# XBee_Explorer_USB.net
KiCad netlist of a schematic drawn in EAGLE
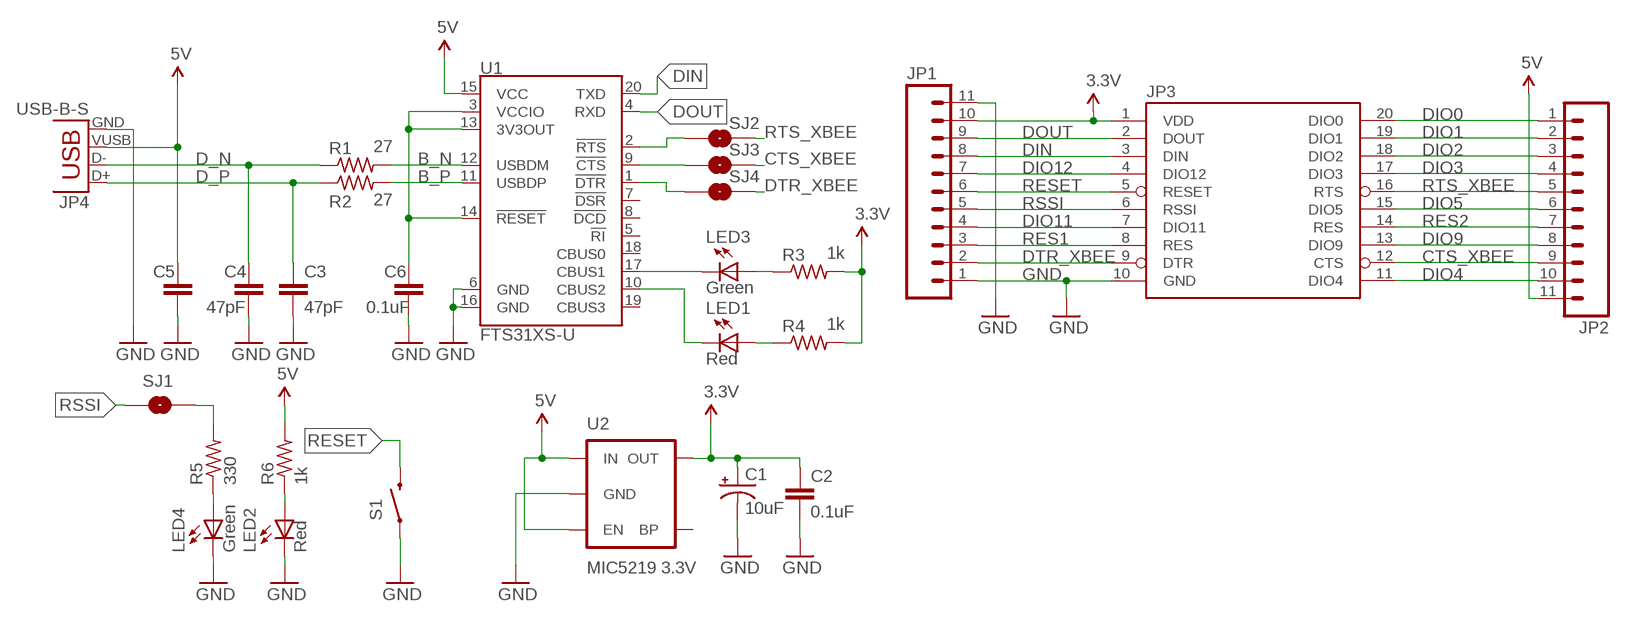
[diagram p0: schematic, sheet 1]

(export (version "E")
  (design (tool "Eeschema 10.0.6"))
  (components
    (comp (ref "C1")
      (value "10uF")
      (footprint "eagle-import:EIA3216")
      (libsource (lib "eagle-import") (part "10UF-16V-10%(TANT)"))
    )
    (comp (ref "C2")
      (value "0.1uF")
      (footprint "eagle-import:0805")
      (libsource (lib "eagle-import") (part "CAP0805"))
    )
    (comp (ref "C3")
      (value "47pF")
      (footprint "eagle-import:0805")
      (libsource (lib "eagle-import") (part "CAP0805"))
    )
    (comp (ref "C4")
      (value "47pF")
      (footprint "eagle-import:0805")
      (libsource (lib "eagle-import") (part "CAP0805"))
    )
    (comp (ref "C5")
      (value "CAP0805")
      (footprint "eagle-import:0805")
      (libsource (lib "eagle-import") (part "CAP0805"))
    )
    (comp (ref "C6")
      (value "0.1uF")
      (footprint "eagle-import:0805")
      (libsource (lib "eagle-import") (part "CAP0805"))
    )
    (comp (ref "JP1")
      (value "M111X11_NO_SILK")
      (footprint "eagle-import:1X11_NO_SILK")
      (libsource (lib "eagle-import") (part "M111X11_NO_SILK"))
    )
    (comp (ref "JP2")
      (value "M111X11_NO_SILK")
      (footprint "eagle-import:1X11_NO_SILK")
      (libsource (lib "eagle-import") (part "M111X11_NO_SILK"))
    )
    (comp (ref "JP3")
      (value "XBEE-1B3")
      (footprint "eagle-import:XBEE-SMD")
      (libsource (lib "eagle-import") (part "XBEE-1B3"))
    )
    (comp (ref "JP4")
      (value "USB-B-S")
      (footprint "eagle-import:USB-B-SMT")
      (libsource (lib "eagle-import") (part "USB-B-S"))
    )
    (comp (ref "LED1")
      (value "Red")
      (footprint "eagle-import:CHIP-LED0805")
      (libsource (lib "eagle-import") (part "LEDCHIP-LED0805"))
    )
    (comp (ref "LED2")
      (value "Red")
      (footprint "eagle-import:CHIP-LED0805")
      (libsource (lib "eagle-import") (part "LEDCHIP-LED0805"))
    )
    (comp (ref "LED3")
      (value "Green")
      (footprint "eagle-import:CHIP-LED0805")
      (libsource (lib "eagle-import") (part "LEDCHIP-LED0805"))
    )
    (comp (ref "LED4")
      (value "Green")
      (footprint "eagle-import:CHIP-LED0805")
      (libsource (lib "eagle-import") (part "LEDCHIP-LED0805"))
    )
    (comp (ref "R1")
      (value "27")
      (footprint "eagle-import:R0805")
      (libsource (lib "eagle-import") (part "R-US_R0805"))
    )
    (comp (ref "R2")
      (value "27")
      (footprint "eagle-import:R0805")
      (libsource (lib "eagle-import") (part "R-US_R0805"))
    )
    (comp (ref "R3")
      (value "1k")
      (footprint "eagle-import:R0805")
      (libsource (lib "eagle-import") (part "R-US_R0805"))
    )
    (comp (ref "R4")
      (value "1k")
      (footprint "eagle-import:R0805")
      (libsource (lib "eagle-import") (part "R-US_R0805"))
    )
    (comp (ref "R5")
      (value "330")
      (footprint "eagle-import:R0805")
      (libsource (lib "eagle-import") (part "R-US_R0805"))
    )
    (comp (ref "R6")
      (value "1k")
      (footprint "eagle-import:R0805")
      (libsource (lib "eagle-import") (part "R-US_R0805"))
    )
    (comp (ref "S1")
      (value "SWITCH-MOMENTARY-2SMD")
      (footprint "eagle-import:TACTILE-SWITCH-SMD")
      (libsource (lib "eagle-import") (part "SWITCH-MOMENTARY-2SMD"))
    )
    (comp (ref "SJ1")
      (value "SOLDERJUMPERTRACE")
      (footprint "eagle-import:SJ_2S-TRACE")
      (libsource (lib "eagle-import") (part "SOLDERJUMPERTRACE"))
    )
    (comp (ref "SJ2")
      (value "SOLDERJUMPERTRACE")
      (footprint "eagle-import:SJ_2S-TRACE")
      (libsource (lib "eagle-import") (part "SOLDERJUMPERTRACE"))
    )
    (comp (ref "SJ3")
      (value "SOLDERJUMPERTRACE")
      (footprint "eagle-import:SJ_2S-TRACE")
      (libsource (lib "eagle-import") (part "SOLDERJUMPERTRACE"))
    )
    (comp (ref "SJ4")
      (value "SOLDERJUMPERTRACE")
      (footprint "eagle-import:SJ_2S-TRACE")
      (libsource (lib "eagle-import") (part "SOLDERJUMPERTRACE"))
    )
    (comp (ref "U1")
      (value "FTS31XS-U")
      (footprint "eagle-import:SSOP20_L")
      (libsource (lib "eagle-import") (part "FT231XS"))
    )
    (comp (ref "U2")
      (value "MIC5219 3.3V")
      (footprint "eagle-import:SOT23-5")
      (libsource (lib "eagle-import") (part "V_REG_MIC52193.3V"))
    )
  )
  (nets
    (net (code "1") (name "/B_N") (class "Default")
      (node (ref "R1") (pin "2") (pinfunction "2_2") (pintype "passive"))
      (node (ref "U1") (pin "12") (pinfunction "USBDM_12") (pintype "bidirectional"))
    )
    (net (code "2") (name "/B_P") (class "Default")
      (node (ref "R2") (pin "2") (pinfunction "2_2") (pintype "passive"))
      (node (ref "U1") (pin "11") (pinfunction "USBDP_11") (pintype "bidirectional"))
    )
    (net (code "3") (name "/CTS_XBEE") (class "Default")
      (node (ref "JP2") (pin "9") (pinfunction "9_9") (pintype "passive"))
      (node (ref "JP3") (pin "12") (pinfunction "CTS_12") (pintype "output"))
      (node (ref "SJ3") (pin "2") (pinfunction "2_2") (pintype "passive"))
    )
    (net (code "4") (name "/DIO0") (class "Default")
      (node (ref "JP2") (pin "1") (pinfunction "1_1") (pintype "passive"))
      (node (ref "JP3") (pin "20") (pinfunction "DIO0_20") (pintype "bidirectional"))
    )
    (net (code "5") (name "/DIO1") (class "Default")
      (node (ref "JP2") (pin "2") (pinfunction "2_2") (pintype "passive"))
      (node (ref "JP3") (pin "19") (pinfunction "DIO1_19") (pintype "bidirectional"))
    )
    (net (code "6") (name "/DIO2") (class "Default")
      (node (ref "JP2") (pin "3") (pinfunction "3_3") (pintype "passive"))
      (node (ref "JP3") (pin "18") (pinfunction "DIO2_18") (pintype "bidirectional"))
    )
    (net (code "7") (name "/DIO3") (class "Default")
      (node (ref "JP2") (pin "4") (pinfunction "4_4") (pintype "passive"))
      (node (ref "JP3") (pin "17") (pinfunction "DIO3_17") (pintype "bidirectional"))
    )
    (net (code "8") (name "/DIO4") (class "Default")
      (node (ref "JP2") (pin "10") (pinfunction "10_10") (pintype "passive"))
      (node (ref "JP3") (pin "11") (pinfunction "DIO4_11") (pintype "bidirectional"))
    )
    (net (code "9") (name "/DIO5") (class "Default")
      (node (ref "JP2") (pin "6") (pinfunction "6_6") (pintype "passive"))
      (node (ref "JP3") (pin "15") (pinfunction "DIO5_15") (pintype "bidirectional"))
    )
    (net (code "10") (name "/DIO9") (class "Default")
      (node (ref "JP2") (pin "8") (pinfunction "8_8") (pintype "passive"))
      (node (ref "JP3") (pin "13") (pinfunction "DIO9_13") (pintype "bidirectional"))
    )
    (net (code "11") (name "/DIO11") (class "Default")
      (node (ref "JP1") (pin "4") (pinfunction "4_4") (pintype "passive"))
      (node (ref "JP3") (pin "7") (pinfunction "DIO11_7") (pintype "bidirectional"))
    )
    (net (code "12") (name "/DIO12") (class "Default")
      (node (ref "JP1") (pin "7") (pinfunction "7_7") (pintype "passive"))
      (node (ref "JP3") (pin "4") (pinfunction "DIO12_4") (pintype "bidirectional"))
    )
    (net (code "13") (name "/DTR_XBEE") (class "Default")
      (node (ref "JP1") (pin "2") (pinfunction "2_2") (pintype "passive"))
      (node (ref "JP3") (pin "9") (pinfunction "DTR_9") (pintype "bidirectional"))
      (node (ref "SJ4") (pin "2") (pinfunction "2_2") (pintype "passive"))
    )
    (net (code "14") (name "/D_N") (class "Default")
      (node (ref "C4") (pin "1") (pinfunction "1_1") (pintype "passive"))
      (node (ref "JP4") (pin "D-") (pinfunction "D-_D-") (pintype "bidirectional"))
      (node (ref "R1") (pin "1") (pinfunction "1_1") (pintype "passive"))
    )
    (net (code "15") (name "/D_P") (class "Default")
      (node (ref "C3") (pin "1") (pinfunction "1_1") (pintype "passive"))
      (node (ref "JP4") (pin "D+") (pinfunction "D+_D+") (pintype "bidirectional"))
      (node (ref "R2") (pin "1") (pinfunction "1_1") (pintype "passive"))
    )
    (net (code "16") (name "/RES1") (class "Default")
      (node (ref "JP1") (pin "3") (pinfunction "3_3") (pintype "passive"))
      (node (ref "JP3") (pin "8") (pinfunction "RES_8") (pintype "bidirectional"))
    )
    (net (code "17") (name "/RES2") (class "Default")
      (node (ref "JP2") (pin "7") (pinfunction "7_7") (pintype "passive"))
      (node (ref "JP3") (pin "14") (pinfunction "RES_14") (pintype "bidirectional"))
    )
    (net (code "18") (name "/RTS_XBEE") (class "Default")
      (node (ref "JP2") (pin "5") (pinfunction "5_5") (pintype "passive"))
      (node (ref "JP3") (pin "16") (pinfunction "RTS_16") (pintype "input"))
      (node (ref "SJ2") (pin "2") (pinfunction "2_2") (pintype "passive"))
    )
    (net (code "19") (name "3.3V") (class "Default")
      (node (ref "C1") (pin "A") (pinfunction "+_A") (pintype "passive"))
      (node (ref "C2") (pin "1") (pinfunction "1_1") (pintype "passive"))
      (node (ref "JP1") (pin "10") (pinfunction "10_10") (pintype "passive"))
      (node (ref "JP3") (pin "1") (pinfunction "VDD_1") (pintype "power_in"))
      (node (ref "R3") (pin "2") (pinfunction "2_2") (pintype "passive"))
      (node (ref "R4") (pin "2") (pinfunction "2_2") (pintype "passive"))
      (node (ref "U2") (pin "5") (pinfunction "OUT_5") (pintype "passive"))
    )
    (net (code "20") (name "5V") (class "Default")
      (node (ref "C5") (pin "1") (pinfunction "1_1") (pintype "passive"))
      (node (ref "JP2") (pin "11") (pinfunction "11_11") (pintype "passive"))
      (node (ref "JP4") (pin "VUSB") (pinfunction "VBUS_VUSB") (pintype "bidirectional"))
      (node (ref "R6") (pin "2") (pinfunction "2_2") (pintype "passive"))
      (node (ref "U1") (pin "15") (pinfunction "VCC_15") (pintype "bidirectional"))
      (node (ref "U2") (pin "1") (pinfunction "IN_1") (pintype "input"))
      (node (ref "U2") (pin "3") (pinfunction "EN_3") (pintype "input"))
    )
    (net (code "21") (name "DIN") (class "Default")
      (node (ref "JP1") (pin "8") (pinfunction "8_8") (pintype "passive"))
      (node (ref "JP3") (pin "3") (pinfunction "DIN_3") (pintype "input"))
      (node (ref "U1") (pin "20") (pinfunction "TXD_20") (pintype "bidirectional"))
    )
    (net (code "22") (name "DOUT") (class "Default")
      (node (ref "JP1") (pin "9") (pinfunction "9_9") (pintype "passive"))
      (node (ref "JP3") (pin "2") (pinfunction "DOUT_2") (pintype "output"))
      (node (ref "U1") (pin "4") (pinfunction "RXD_4") (pintype "bidirectional"))
    )
    (net (code "23") (name "GND") (class "Default")
      (node (ref "C1") (pin "C") (pinfunction "-_C") (pintype "passive"))
      (node (ref "C2") (pin "2") (pinfunction "2_2") (pintype "passive"))
      (node (ref "C3") (pin "2") (pinfunction "2_2") (pintype "passive"))
      (node (ref "C4") (pin "2") (pinfunction "2_2") (pintype "passive"))
      (node (ref "C5") (pin "2") (pinfunction "2_2") (pintype "passive"))
      (node (ref "C6") (pin "2") (pinfunction "2_2") (pintype "passive"))
      (node (ref "JP1") (pin "1") (pinfunction "1_1") (pintype "passive"))
      (node (ref "JP1") (pin "11") (pinfunction "11_11") (pintype "passive"))
      (node (ref "JP3") (pin "10") (pinfunction "GND_10") (pintype "power_in"))
      (node (ref "JP4") (pin "GND") (pinfunction "GND_GND") (pintype "bidirectional"))
      (node (ref "LED2") (pin "C") (pinfunction "C_C") (pintype "passive"))
      (node (ref "LED4") (pin "C") (pinfunction "C_C") (pintype "passive"))
      (node (ref "S1") (pin "1") (pinfunction "1_1") (pintype "passive"))
      (node (ref "U1") (pin "16") (pinfunction "GND_16") (pintype "bidirectional"))
      (node (ref "U1") (pin "6") (pinfunction "GND_6") (pintype "bidirectional"))
      (node (ref "U2") (pin "2") (pinfunction "GND_2") (pintype "input"))
    )
    (net (code "24") (name "Net-(LED1-PadA)") (class "Default")
      (node (ref "LED1") (pin "A") (pinfunction "A_A") (pintype "passive"))
      (node (ref "R4") (pin "1") (pinfunction "1_1") (pintype "passive"))
    )
    (net (code "25") (name "Net-(LED2-PadA)") (class "Default")
      (node (ref "LED2") (pin "A") (pinfunction "A_A") (pintype "passive"))
      (node (ref "R6") (pin "1") (pinfunction "1_1") (pintype "passive"))
    )
    (net (code "26") (name "Net-(LED3-PadA)") (class "Default")
      (node (ref "LED3") (pin "A") (pinfunction "A_A") (pintype "passive"))
      (node (ref "R3") (pin "1") (pinfunction "1_1") (pintype "passive"))
    )
    (net (code "27") (name "Net-(LED4-PadA)") (class "Default")
      (node (ref "LED4") (pin "A") (pinfunction "A_A") (pintype "passive"))
      (node (ref "R5") (pin "1") (pinfunction "1_1") (pintype "passive"))
    )
    (net (code "28") (name "Net-(R5-Pad2)") (class "Default")
      (node (ref "R5") (pin "2") (pinfunction "2_2") (pintype "passive"))
      (node (ref "SJ1") (pin "2") (pinfunction "2_2") (pintype "passive"))
    )
    (net (code "29") (name "Net-(U1-3V3OUT)") (class "Default")
      (node (ref "C6") (pin "1") (pinfunction "1_1") (pintype "passive"))
      (node (ref "U1") (pin "13") (pinfunction "3V3OUT_13") (pintype "bidirectional"))
      (node (ref "U1") (pin "14") (pinfunction "~{RESET}_14") (pintype "bidirectional"))
      (node (ref "U1") (pin "3") (pinfunction "VCCIO_3") (pintype "bidirectional"))
    )
    (net (code "30") (name "Net-(U1-CBUS1)") (class "Default")
      (node (ref "LED3") (pin "C") (pinfunction "C_C") (pintype "passive"))
      (node (ref "U1") (pin "17") (pinfunction "CBUS1_17") (pintype "bidirectional"))
    )
    (net (code "31") (name "Net-(U1-CBUS2)") (class "Default")
      (node (ref "LED1") (pin "C") (pinfunction "C_C") (pintype "passive"))
      (node (ref "U1") (pin "10") (pinfunction "CBUS2_10") (pintype "bidirectional"))
    )
    (net (code "32") (name "Net-(U1-~{CTS})") (class "Default")
      (node (ref "SJ3") (pin "1") (pinfunction "1_1") (pintype "passive"))
      (node (ref "U1") (pin "9") (pinfunction "~{CTS}_9") (pintype "bidirectional"))
    )
    (net (code "33") (name "Net-(U1-~{DTR})") (class "Default")
      (node (ref "SJ4") (pin "1") (pinfunction "1_1") (pintype "passive"))
      (node (ref "U1") (pin "1") (pinfunction "~{DTR}_1") (pintype "bidirectional"))
    )
    (net (code "34") (name "Net-(U1-~{RTS})") (class "Default")
      (node (ref "SJ2") (pin "1") (pinfunction "1_1") (pintype "passive"))
      (node (ref "U1") (pin "2") (pinfunction "~{RTS}_2") (pintype "bidirectional"))
    )
    (net (code "35") (name "RESET") (class "Default")
      (node (ref "JP1") (pin "6") (pinfunction "6_6") (pintype "passive"))
      (node (ref "JP3") (pin "5") (pinfunction "RESET_5") (pintype "input"))
      (node (ref "S1") (pin "3") (pinfunction "2_3") (pintype "passive"))
    )
    (net (code "36") (name "RSSI") (class "Default")
      (node (ref "JP1") (pin "5") (pinfunction "5_5") (pintype "passive"))
      (node (ref "JP3") (pin "6") (pinfunction "RSSI_6") (pintype "bidirectional"))
      (node (ref "SJ1") (pin "1") (pinfunction "1_1") (pintype "passive"))
    )
    (net (code "37") (name "unconnected-(U1-CBUS0-Pad18)") (class "Default")
      (node (ref "U1") (pin "18") (pinfunction "CBUS0_18") (pintype "bidirectional"))
    )
    (net (code "38") (name "unconnected-(U1-CBUS3-Pad19)") (class "Default")
      (node (ref "U1") (pin "19") (pinfunction "CBUS3_19") (pintype "bidirectional"))
    )
    (net (code "39") (name "unconnected-(U1-~{DCD}-Pad8)") (class "Default")
      (node (ref "U1") (pin "8") (pinfunction "~{DCD}_8") (pintype "bidirectional"))
    )
    (net (code "40") (name "unconnected-(U1-~{DSR}-Pad7)") (class "Default")
      (node (ref "U1") (pin "7") (pinfunction "~{DSR}_7") (pintype "bidirectional"))
    )
    (net (code "41") (name "unconnected-(U1-~{RI}-Pad5)") (class "Default")
      (node (ref "U1") (pin "5") (pinfunction "~{RI}_5") (pintype "bidirectional"))
    )
    (net (code "42") (name "unconnected-(U2-BP-Pad4)") (class "Default")
      (node (ref "U2") (pin "4") (pinfunction "BP_4") (pintype "input"))
    )
  )
)
